# AFE.net
KiCad netlist of a schematic drawn in Altium Designer
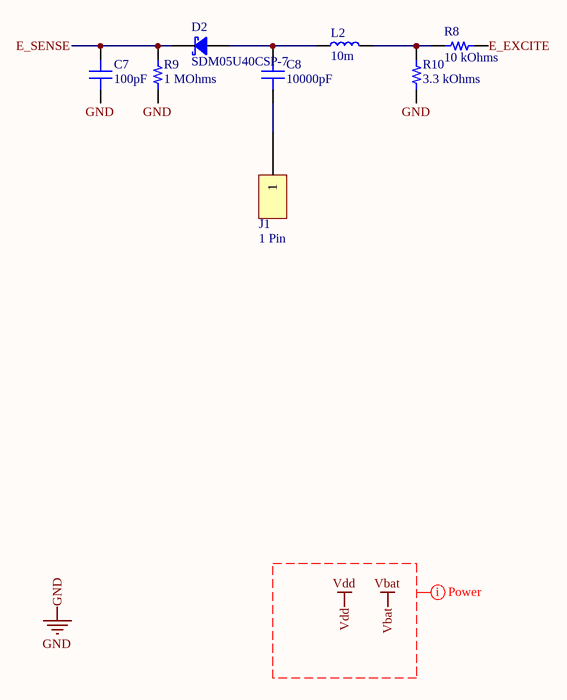
[diagram p0: AFE.SchDoc]

(export (version "E")
  (design (tool "Eeschema 10.0.6"))
  (components
    (comp (ref "C7")
      (value "100pF")
      (footprint "CAP 0201_0603")
      (description "CAP CER 100PF 50V C0G/NP0 0201")
      (fields
        (field (name "PART NUMBER") "GRM0335C1H101GA01D")
        (field (name "MANUFACTURER") "Murata Electronics")
      )
      (libsource (lib "Celestial Altium Library") (part "Capacitor"))
    )
    (comp (ref "C8")
      (value "10000pF")
      (footprint "CAP 0201_0603")
      (description "CAP CER 10000PF 10V X5R 0201")
      (fields
        (field (name "PART NUMBER") "GRM033R61A103KA01D")
        (field (name "MANUFACTURER") "Murata Electronics")
      )
      (libsource (lib "Celestial Altium Library") (part "Capacitor"))
    )
    (comp (ref "D2")
      (value "SDM05U40CSP-7")
      (footprint "DIODES X3-WLB1006-2")
      (description "DIODE SCHTKY 40V 0.5A X3WLB1006")
      (fields (field (name "MANUFACTURER") "Diodes"))
      (libsource (lib "ekuore-library") (part "Diode Schottky"))
    )
    (comp (ref "J1")
      (value "1 Pin")
      (footprint "HARWIN P70-5100045R")
      (description "POGO PIN 4MM SMD")
      (fields (field (name "PART NUMBER") "P70-5100045R") (field (name "MANUFACTURER") "Harwin"))
      (libsource (lib "ekuore-library") (part "1 Pin"))
    )
    (comp (ref "L2")
      (value "10m")
      (footprint "IND BOURNS SDR0503")
      (description "IND (0503) 10mH +-5% 0.04A 110R")
      (fields (field (name "PART NUMBER") "SDR0503-103JL") (field (name "MANUFACTURER") "Bourns"))
      (libsource (lib "ekuore-library") (part "Inductor"))
    )
    (comp (ref "R8")
      (value "10 kOhms")
      (footprint "RES 0201_0603")
      (description "RES SMD 10K OHM 1% 1/20W 0201")
      (fields (field (name "PART NUMBER") "CRCW020110K0FNED") (field (name "MANUFACTURER") "Vishay Dale"))
      (libsource (lib "Celestial Altium Library") (part "Resistor"))
    )
    (comp (ref "R9")
      (value "1 MOhms")
      (footprint "RES 0201_0603")
      (description "RES 1M OHM 1% 1/20W 0201")
      (fields
        (field (name "PART NUMBER") "RMCF0201FT1M00")
        (field (name "MANUFACTURER") "Stackpole Electronics Inc")
      )
      (libsource (lib "Celestial Altium Library") (part "Resistor"))
    )
    (comp (ref "R10")
      (value "3.3 kOhms")
      (footprint "RES 0201_0603")
      (description "RES SMD 3.3K OHM 1% 1/20W 0201")
      (fields (field (name "PART NUMBER") "CRCW02013K30FNED") (field (name "MANUFACTURER") "Vishay Dale"))
      (libsource (lib "Celestial Altium Library") (part "Resistor"))
    )
  )
  (nets
    (net (code "1") (name "/E_EXCITE") (class "Default")
      (node (ref "R8") (pin "2") (pinfunction "2_2") (pintype "passive"))
    )
    (net (code "2") (name "/E_SENSE") (class "Default")
      (node (ref "C7") (pin "2") (pinfunction "2_2") (pintype "passive"))
      (node (ref "D2") (pin "1") (pinfunction "K_1") (pintype "passive"))
      (node (ref "R9") (pin "1") (pinfunction "1_1") (pintype "passive"))
    )
    (net (code "3") (name "GND") (class "Default")
      (node (ref "C7") (pin "1") (pinfunction "1_1") (pintype "passive"))
      (node (ref "R10") (pin "1") (pinfunction "1_1") (pintype "passive"))
      (node (ref "R9") (pin "2") (pinfunction "2_2") (pintype "passive"))
    )
    (net (code "4") (name "Net-(C8-Pad2)") (class "Default")
      (node (ref "C8") (pin "2") (pinfunction "2_2") (pintype "passive"))
      (node (ref "J1") (pin "1") (pinfunction "1_1") (pintype "passive"))
    )
    (net (code "5") (name "Net-(D2-A)") (class "Default")
      (node (ref "C8") (pin "1") (pinfunction "1_1") (pintype "passive"))
      (node (ref "D2") (pin "2") (pinfunction "A_2") (pintype "passive"))
      (node (ref "L2") (pin "1") (pinfunction "1_1") (pintype "passive"))
    )
    (net (code "6") (name "Net-(L2-Pad2)") (class "Default")
      (node (ref "L2") (pin "2") (pinfunction "2_2") (pintype "passive"))
      (node (ref "R10") (pin "2") (pinfunction "2_2") (pintype "passive"))
      (node (ref "R8") (pin "1") (pinfunction "1_1") (pintype "passive"))
    )
  )
)
